# sodonguyenly.net
KiCad netlist of a schematic drawn in Altium Designer
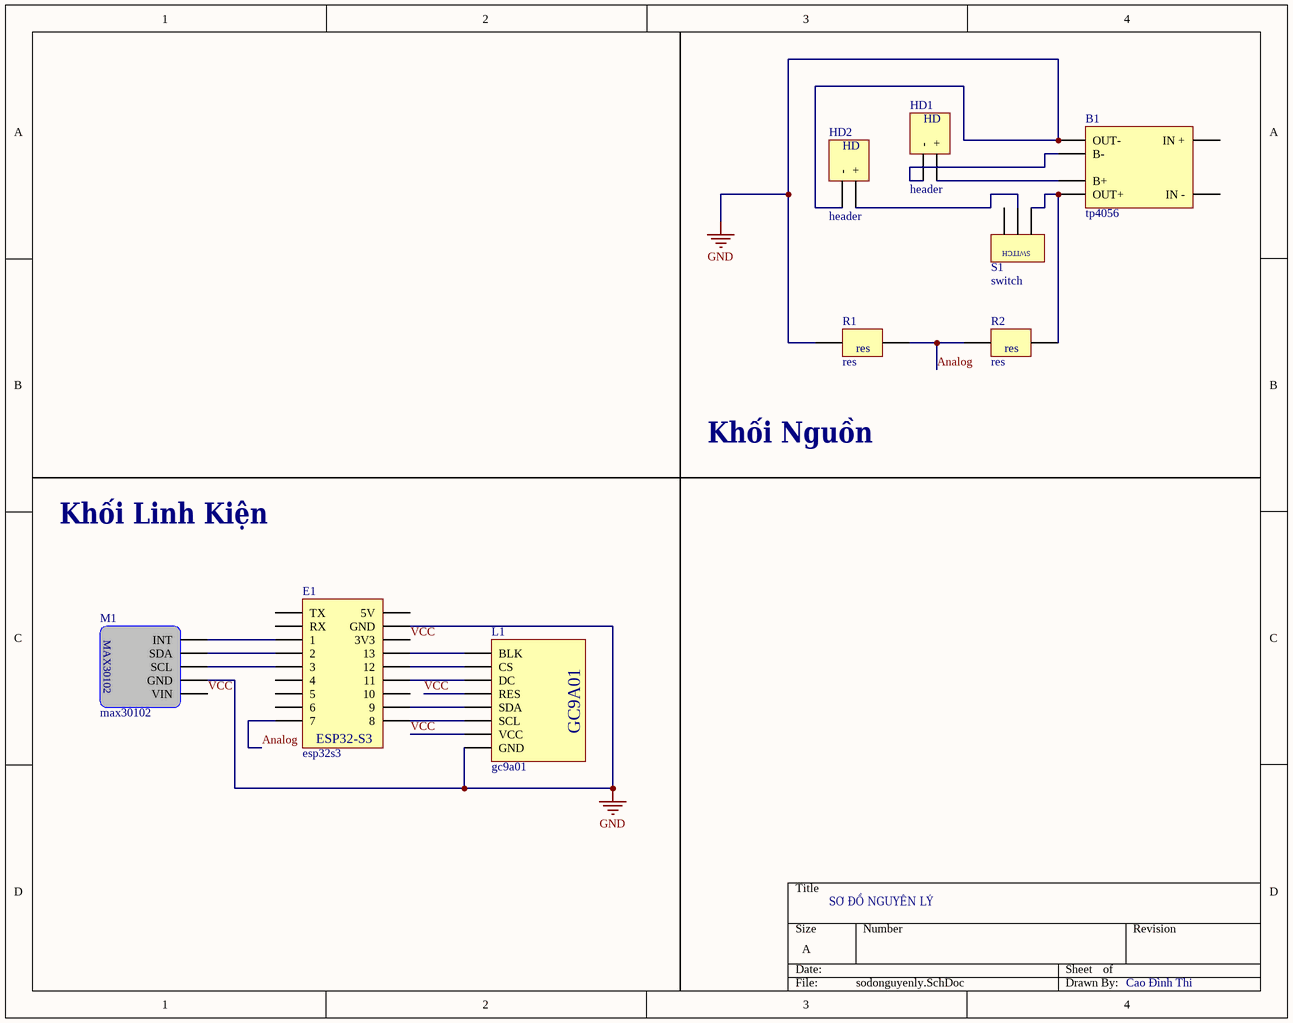
[diagram p0: sodonguyenly.SchDoc]

(export (version "E")
  (design (tool "Eeschema 10.0.6"))
  (components
    (comp (ref "B1") (value "tp4056") (footprint "tp4056") (libsource (lib "tp4056") (part "tp4056")))
    (comp (ref "E1") (value "esp32s3") (footprint "esp32s3") (libsource (lib "esp32s3") (part "esp32s3")))
    (comp (ref "HD1") (value "header") (footprint "header") (libsource (lib "header") (part "header")))
    (comp (ref "HD2") (value "header") (footprint "header") (libsource (lib "header") (part "header")))
    (comp (ref "L1") (value "gc9a01") (footprint "gc9a01") (libsource (lib "gc9a01") (part "gc9a01")))
    (comp (ref "M1") (value "max30102") (footprint "max30102") (libsource (lib "max30102") (part "max30102")))
    (comp (ref "R1") (value "res") (footprint "res") (libsource (lib "res") (part "res")))
    (comp (ref "R2") (value "res") (footprint "res") (libsource (lib "res") (part "res")))
    (comp (ref "S1") (value "switch") (footprint "switch") (libsource (lib "switch") (part "switch")))
  )
  (nets
    (net (code "1") (name "/Analog") (class "Default")
      (node (ref "E1") (pin "8") (pinfunction "7_8") (pintype "passive"))
      (node (ref "R1") (pin "1") (pinfunction "1_1") (pintype "passive"))
      (node (ref "R2") (pin "0") (pinfunction "0_0") (pintype "passive"))
    )
    (net (code "2") (name "/VCC") (class "Default")
      (node (ref "E1") (pin "15") (pinfunction "3V3_15") (pintype "passive"))
      (node (ref "L1") (pin "1") (pinfunction "VCC_1") (pintype "passive"))
      (node (ref "L1") (pin "4") (pinfunction "RES_4") (pintype "passive"))
      (node (ref "M1") (pin "4") (pinfunction "VIN_4") (pintype "passive"))
    )
    (net (code "3") (name "GND") (class "Default")
      (node (ref "B1") (pin "2") (pinfunction "OUT-_2") (pintype "passive"))
      (node (ref "E1") (pin "16") (pinfunction "GND_16") (pintype "passive"))
      (node (ref "HD2") (pin "0") (pinfunction "-_0") (pintype "passive"))
      (node (ref "L1") (pin "0") (pinfunction "GND_0") (pintype "passive"))
      (node (ref "M1") (pin "3") (pinfunction "GND_3") (pintype "passive"))
      (node (ref "R1") (pin "0") (pinfunction "0_0") (pintype "passive"))
    )
    (net (code "4") (name "Net-(B1-B+)") (class "Default")
      (node (ref "B1") (pin "4") (pinfunction "B+_4") (pintype "passive"))
      (node (ref "HD1") (pin "1") (pinfunction "+_1") (pintype "passive"))
    )
    (net (code "5") (name "Net-(B1-B-)") (class "Default")
      (node (ref "B1") (pin "3") (pinfunction "B-_3") (pintype "passive"))
      (node (ref "HD1") (pin "0") (pinfunction "-_0") (pintype "passive"))
    )
    (net (code "6") (name "Net-(B1-OUT+)") (class "Default")
      (node (ref "B1") (pin "5") (pinfunction "OUT+_5") (pintype "passive"))
      (node (ref "R2") (pin "1") (pinfunction "1_1") (pintype "passive"))
      (node (ref "S1") (pin "0") (pinfunction "0_0") (pintype "passive"))
    )
    (net (code "7") (name "Net-(E1-1)") (class "Default")
      (node (ref "E1") (pin "2") (pinfunction "1_2") (pintype "passive"))
      (node (ref "M1") (pin "0") (pinfunction "INT_0") (pintype "passive"))
    )
    (net (code "8") (name "Net-(E1-2)") (class "Default")
      (node (ref "E1") (pin "3") (pinfunction "2_3") (pintype "passive"))
      (node (ref "M1") (pin "1") (pinfunction "SDA_1") (pintype "passive"))
    )
    (net (code "9") (name "Net-(E1-3)") (class "Default")
      (node (ref "E1") (pin "4") (pinfunction "3_4") (pintype "passive"))
      (node (ref "M1") (pin "2") (pinfunction "SCL_2") (pintype "passive"))
    )
    (net (code "10") (name "Net-(E1-8)") (class "Default")
      (node (ref "E1") (pin "9") (pinfunction "8_9") (pintype "passive"))
      (node (ref "L1") (pin "2") (pinfunction "SCL_2") (pintype "passive"))
    )
    (net (code "11") (name "Net-(E1-9)") (class "Default")
      (node (ref "E1") (pin "10") (pinfunction "9_10") (pintype "passive"))
      (node (ref "L1") (pin "3") (pinfunction "SDA_3") (pintype "passive"))
    )
    (net (code "12") (name "Net-(E1-11)") (class "Default")
      (node (ref "E1") (pin "12") (pinfunction "11_12") (pintype "passive"))
      (node (ref "L1") (pin "5") (pinfunction "DC_5") (pintype "passive"))
    )
    (net (code "13") (name "Net-(E1-12)") (class "Default")
      (node (ref "E1") (pin "13") (pinfunction "12_13") (pintype "passive"))
      (node (ref "L1") (pin "6") (pinfunction "CS_6") (pintype "passive"))
    )
    (net (code "14") (name "Net-(E1-13)") (class "Default")
      (node (ref "E1") (pin "14") (pinfunction "13_14") (pintype "passive"))
      (node (ref "L1") (pin "7") (pinfunction "BLK_7") (pintype "passive"))
    )
    (net (code "15") (name "Net-(HD2-+)") (class "Default")
      (node (ref "HD2") (pin "1") (pinfunction "+_1") (pintype "passive"))
      (node (ref "S1") (pin "1") (pinfunction "1_1") (pintype "passive"))
    )
    (net (code "16") (name "unconnected-(B1-IN_+-Pad0)") (class "Default")
      (node (ref "B1") (pin "0") (pinfunction "IN_+_0") (pintype "passive"))
    )
    (net (code "17") (name "unconnected-(B1-IN_--Pad1)") (class "Default")
      (node (ref "B1") (pin "1") (pinfunction "IN_-_1") (pintype "passive"))
    )
    (net (code "18") (name "unconnected-(E1-4-Pad5)") (class "Default")
      (node (ref "E1") (pin "5") (pinfunction "4_5") (pintype "passive"))
    )
    (net (code "19") (name "unconnected-(E1-5-Pad6)") (class "Default")
      (node (ref "E1") (pin "6") (pinfunction "5_6") (pintype "passive"))
    )
    (net (code "20") (name "unconnected-(E1-5V-Pad17)") (class "Default")
      (node (ref "E1") (pin "17") (pinfunction "5V_17") (pintype "passive"))
    )
    (net (code "21") (name "unconnected-(E1-6-Pad7)") (class "Default")
      (node (ref "E1") (pin "7") (pinfunction "6_7") (pintype "passive"))
    )
    (net (code "22") (name "unconnected-(E1-10-Pad11)") (class "Default")
      (node (ref "E1") (pin "11") (pinfunction "10_11") (pintype "passive"))
    )
    (net (code "23") (name "unconnected-(E1-RX-Pad1)") (class "Default")
      (node (ref "E1") (pin "1") (pinfunction "RX_1") (pintype "passive"))
    )
    (net (code "24") (name "unconnected-(E1-TX-Pad0)") (class "Default")
      (node (ref "E1") (pin "0") (pinfunction "TX_0") (pintype "passive"))
    )
    (net (code "25") (name "unconnected-(S1-Pad2)") (class "Default")
      (node (ref "S1") (pin "2") (pinfunction "2_2") (pintype "passive"))
    )
  )
)
